# Micro_Power_Distribution.net
KiCad netlist of a schematic drawn in EAGLE
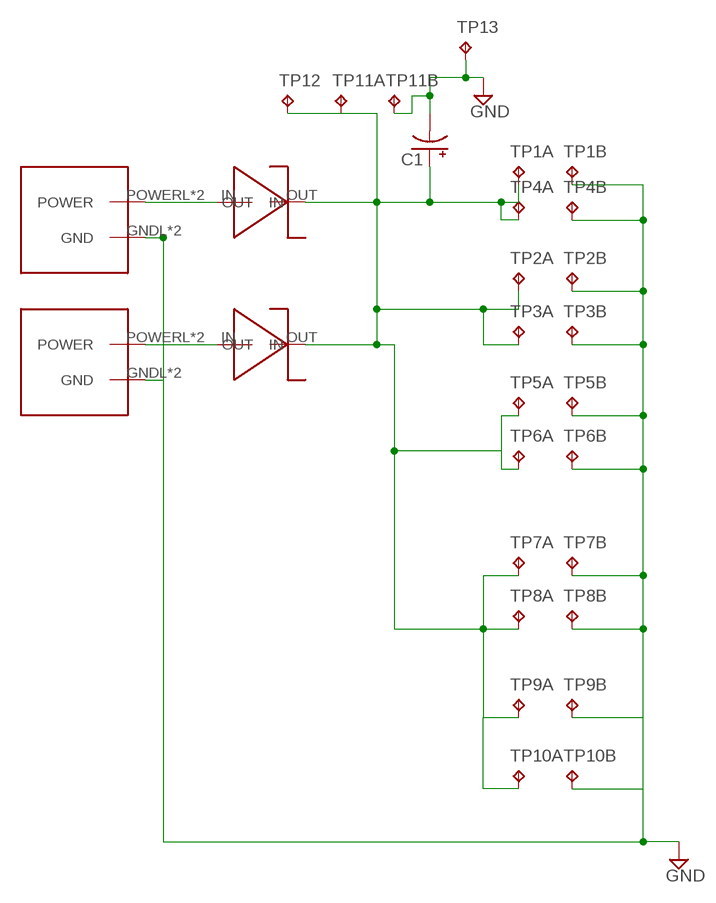
[diagram p0: schematic, sheet 1]

(export (version "E")
  (design (tool "Eeschema 10.0.6"))
  (components
    (comp (ref "C1")
      (value "CPOL-USE2.5-6")
      (footprint "eagle-import:E2,5-6")
      (libsource (lib "eagle-import") (part "CPOL-USE2.5-6"))
    )
    (comp (ref "TP1")
      (value "TP2P2-38-17")
      (footprint "eagle-import:P2-38-17")
      (libsource (lib "eagle-import") (part "TP2P2-38-17"))
    )
    (comp (ref "TP2")
      (value "TP2P2-38-17")
      (footprint "eagle-import:P2-38-17")
      (libsource (lib "eagle-import") (part "TP2P2-38-17"))
    )
    (comp (ref "TP3")
      (value "TP2P2-38-17")
      (footprint "eagle-import:P2-38-17")
      (libsource (lib "eagle-import") (part "TP2P2-38-17"))
    )
    (comp (ref "TP4")
      (value "TP2P2-38-17")
      (footprint "eagle-import:P2-38-17")
      (libsource (lib "eagle-import") (part "TP2P2-38-17"))
    )
    (comp (ref "TP5")
      (value "TP2P2-38-17")
      (footprint "eagle-import:P2-38-17")
      (libsource (lib "eagle-import") (part "TP2P2-38-17"))
    )
    (comp (ref "TP6")
      (value "TP2P2-38-17")
      (footprint "eagle-import:P2-38-17")
      (libsource (lib "eagle-import") (part "TP2P2-38-17"))
    )
    (comp (ref "TP7")
      (value "TP2P2-38-17")
      (footprint "eagle-import:P2-38-17")
      (libsource (lib "eagle-import") (part "TP2P2-38-17"))
    )
    (comp (ref "TP8")
      (value "TP2P2-38-17")
      (footprint "eagle-import:P2-38-17")
      (libsource (lib "eagle-import") (part "TP2P2-38-17"))
    )
    (comp (ref "TP9")
      (value "TP2P2-38-17")
      (footprint "eagle-import:P2-38-17")
      (libsource (lib "eagle-import") (part "TP2P2-38-17"))
    )
    (comp (ref "TP10")
      (value "TP2P2-38-17")
      (footprint "eagle-import:P2-38-17")
      (libsource (lib "eagle-import") (part "TP2P2-38-17"))
    )
    (comp (ref "TP11")
      (value "TP2P2-38-17")
      (footprint "eagle-import:P2-38-17")
      (libsource (lib "eagle-import") (part "TP2P2-38-17"))
    )
    (comp (ref "TP12")
      (value "TPTP20SQ")
      (footprint "eagle-import:TP20SQ")
      (libsource (lib "eagle-import") (part "TPTP20SQ"))
    )
    (comp (ref "TP13")
      (value "TPTP20SQ")
      (footprint "eagle-import:TP20SQ")
      (libsource (lib "eagle-import") (part "TPTP20SQ"))
    )
    (comp (ref "U$1")
      (value "2X2-MOLEX")
      (footprint "eagle-import:2X2MOLEX")
      (libsource (lib "eagle-import") (part "2X2-MOLEX"))
    )
    (comp (ref "U$5")
      (value "2X2-MOLEX")
      (footprint "eagle-import:2X2MOLEX")
      (libsource (lib "eagle-import") (part "2X2-MOLEX"))
    )
    (comp (ref "U$6")
      (value "DO-214AB")
      (footprint "eagle-import:DO-214AB")
      (libsource (lib "eagle-import") (part "DO-214AB"))
    )
    (comp (ref "U$7")
      (value "DO-214AB")
      (footprint "eagle-import:DO-214AB")
      (libsource (lib "eagle-import") (part "DO-214AB"))
    )
  )
  (nets
    (net (code "1") (name "GND") (class "Default")
      (node (ref "C1") (pin "-") (pinfunction "-_-") (pintype "passive"))
      (node (ref "TP1") (pin "TP-2") (pinfunction "TP_TP-2") (pintype "input"))
      (node (ref "TP10") (pin "TP-2") (pinfunction "TP_TP-2") (pintype "input"))
      (node (ref "TP11") (pin "TP-2") (pinfunction "TP_TP-2") (pintype "input"))
      (node (ref "TP13") (pin "TP") (pinfunction "TP_TP") (pintype "input"))
      (node (ref "TP2") (pin "TP-2") (pinfunction "TP_TP-2") (pintype "input"))
      (node (ref "TP3") (pin "TP-2") (pinfunction "TP_TP-2") (pintype "input"))
      (node (ref "TP4") (pin "TP-2") (pinfunction "TP_TP-2") (pintype "input"))
      (node (ref "TP5") (pin "TP-2") (pinfunction "TP_TP-2") (pintype "input"))
      (node (ref "TP6") (pin "TP-2") (pinfunction "TP_TP-2") (pintype "input"))
      (node (ref "TP7") (pin "TP-2") (pinfunction "TP_TP-2") (pintype "input"))
      (node (ref "TP8") (pin "TP-2") (pinfunction "TP_TP-2") (pintype "input"))
      (node (ref "TP9") (pin "TP-2") (pinfunction "TP_TP-2") (pintype "input"))
      (node (ref "U$1") (pin "GNDL") (pinfunction "GND_GNDL") (pintype "bidirectional"))
      (node (ref "U$1") (pin "GNDR") (pinfunction "GND_GNDR") (pintype "bidirectional"))
      (node (ref "U$5") (pin "GNDL") (pinfunction "GND_GNDL") (pintype "bidirectional"))
      (node (ref "U$5") (pin "GNDR") (pinfunction "GND_GNDR") (pintype "bidirectional"))
    )
    (net (code "2") (name "Net-(TP10A-TP)") (class "Default")
      (node (ref "C1") (pin "+") (pinfunction "+_+") (pintype "passive"))
      (node (ref "TP1") (pin "TP-1") (pinfunction "TP_TP-1") (pintype "input"))
      (node (ref "TP10") (pin "TP-1") (pinfunction "TP_TP-1") (pintype "input"))
      (node (ref "TP11") (pin "TP-1") (pinfunction "TP_TP-1") (pintype "input"))
      (node (ref "TP12") (pin "TP") (pinfunction "TP_TP") (pintype "input"))
      (node (ref "TP2") (pin "TP-1") (pinfunction "TP_TP-1") (pintype "input"))
      (node (ref "TP3") (pin "TP-1") (pinfunction "TP_TP-1") (pintype "input"))
      (node (ref "TP4") (pin "TP-1") (pinfunction "TP_TP-1") (pintype "input"))
      (node (ref "TP5") (pin "TP-1") (pinfunction "TP_TP-1") (pintype "input"))
      (node (ref "TP6") (pin "TP-1") (pinfunction "TP_TP-1") (pintype "input"))
      (node (ref "TP7") (pin "TP-1") (pinfunction "TP_TP-1") (pintype "input"))
      (node (ref "TP8") (pin "TP-1") (pinfunction "TP_TP-1") (pintype "input"))
      (node (ref "TP9") (pin "TP-1") (pinfunction "TP_TP-1") (pintype "input"))
      (node (ref "U$6") (pin "OUT") (pinfunction "OUT_OUT") (pintype "bidirectional"))
      (node (ref "U$7") (pin "OUT") (pinfunction "OUT_OUT") (pintype "bidirectional"))
    )
    (net (code "3") (name "Net-(U$1-POWER-PadPOWERL)") (class "Default")
      (node (ref "U$1") (pin "POWERL") (pinfunction "POWER_POWERL") (pintype "bidirectional"))
      (node (ref "U$1") (pin "POWERR") (pinfunction "POWER_POWERR") (pintype "bidirectional"))
      (node (ref "U$7") (pin "IN") (pinfunction "IN_IN") (pintype "bidirectional"))
    )
    (net (code "4") (name "Net-(U$5-POWER-PadPOWERL)") (class "Default")
      (node (ref "U$5") (pin "POWERL") (pinfunction "POWER_POWERL") (pintype "bidirectional"))
      (node (ref "U$5") (pin "POWERR") (pinfunction "POWER_POWERR") (pintype "bidirectional"))
      (node (ref "U$6") (pin "IN") (pinfunction "IN_IN") (pintype "bidirectional"))
    )
  )
)
